# mcu-io.net
KiCad netlist of a schematic drawn in Altium Designer
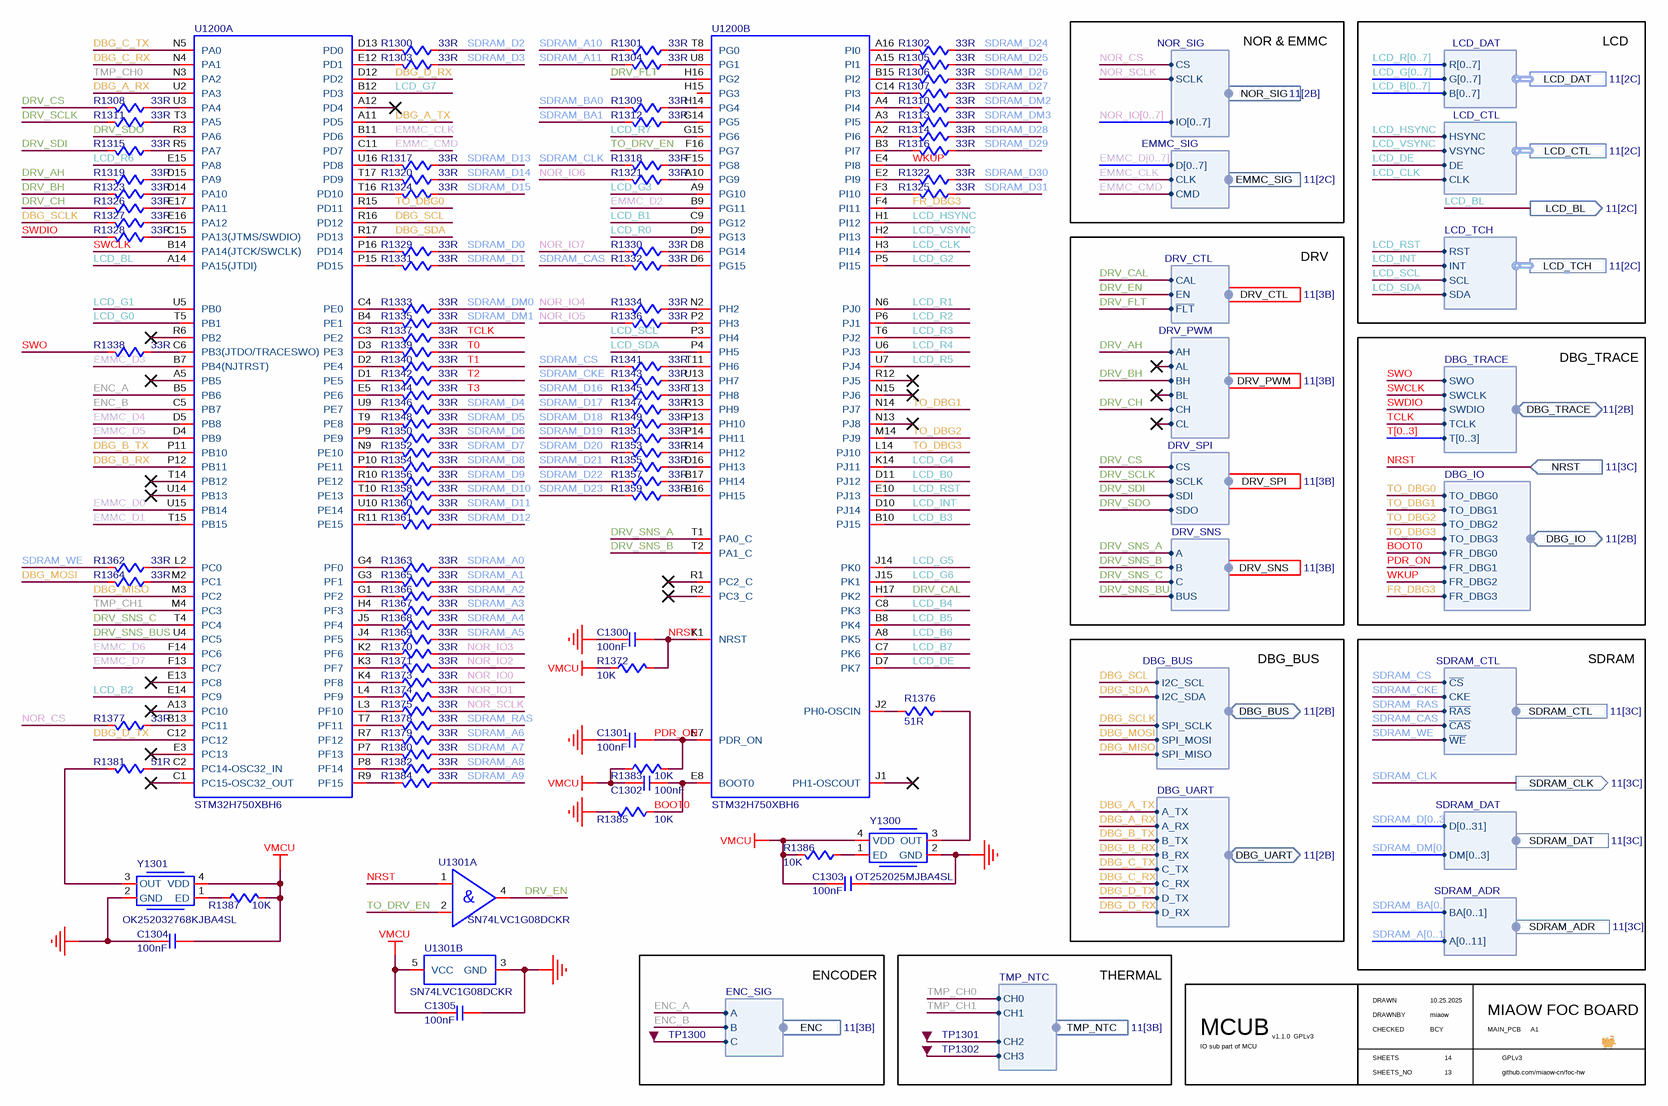
[diagram p0: mcu-io.schdoc]

(export (version "E")
  (design (tool "Eeschema 10.0.6"))
  (components
    (comp (ref "C1300")
      (value "100nF")
      (footprint "mw:C0402")
      (fields (field (name "VOLTAGE") "25V") (field (name "Comment") "C-NOMO"))
      (libsource (lib "mw") (part "C-NOMO"))
    )
    (comp (ref "C1301")
      (value "100nF")
      (footprint "mw:C0402")
      (fields (field (name "VOLTAGE") "25V") (field (name "Comment") "C-NOMO"))
      (libsource (lib "mw") (part "C-NOMO"))
    )
    (comp (ref "C1302")
      (value "100nF")
      (footprint "mw:C0402")
      (fields (field (name "VOLTAGE") "25V") (field (name "Comment") "C-NOMO"))
      (libsource (lib "mw") (part "C-NOMO"))
    )
    (comp (ref "C1303")
      (value "100nF")
      (footprint "mw:C0402")
      (fields (field (name "VOLTAGE") "25V") (field (name "Comment") "C-NOMO"))
      (libsource (lib "mw") (part "C-NOMO"))
    )
    (comp (ref "C1304")
      (value "100nF")
      (footprint "mw:C0402")
      (fields (field (name "VOLTAGE") "25V") (field (name "Comment") "C-NOMO"))
      (libsource (lib "mw") (part "C-NOMO"))
    )
    (comp (ref "C1305")
      (value "100nF")
      (footprint "mw:C0402")
      (fields (field (name "VOLTAGE") "25V") (field (name "Comment") "C-NOMO"))
      (libsource (lib "mw") (part "C-NOMO"))
    )
    (comp (ref "R1300")
      (value "33R")
      (footprint "mw:R0402")
      (fields (field (name "Comment") "R"))
      (libsource (lib "mw") (part "R"))
    )
    (comp (ref "R1301")
      (value "33R")
      (footprint "mw:R0402")
      (fields (field (name "Comment") "R"))
      (libsource (lib "mw") (part "R"))
    )
    (comp (ref "R1302")
      (value "33R")
      (footprint "mw:R0402")
      (fields (field (name "Comment") "R"))
      (libsource (lib "mw") (part "R"))
    )
    (comp (ref "R1303")
      (value "33R")
      (footprint "mw:R0402")
      (fields (field (name "Comment") "R"))
      (libsource (lib "mw") (part "R"))
    )
    (comp (ref "R1304")
      (value "33R")
      (footprint "mw:R0402")
      (fields (field (name "Comment") "R"))
      (libsource (lib "mw") (part "R"))
    )
    (comp (ref "R1305")
      (value "33R")
      (footprint "mw:R0402")
      (fields (field (name "Comment") "R"))
      (libsource (lib "mw") (part "R"))
    )
    (comp (ref "R1306")
      (value "33R")
      (footprint "mw:R0402")
      (fields (field (name "Comment") "R"))
      (libsource (lib "mw") (part "R"))
    )
    (comp (ref "R1307")
      (value "33R")
      (footprint "mw:R0402")
      (fields (field (name "Comment") "R"))
      (libsource (lib "mw") (part "R"))
    )
    (comp (ref "R1308")
      (value "33R")
      (footprint "mw:R0402")
      (fields (field (name "Comment") "R"))
      (libsource (lib "mw") (part "R"))
    )
    (comp (ref "R1309")
      (value "33R")
      (footprint "mw:R0402")
      (fields (field (name "Comment") "R"))
      (libsource (lib "mw") (part "R"))
    )
    (comp (ref "R1310")
      (value "33R")
      (footprint "mw:R0402")
      (fields (field (name "Comment") "R"))
      (libsource (lib "mw") (part "R"))
    )
    (comp (ref "R1311")
      (value "33R")
      (footprint "mw:R0402")
      (fields (field (name "Comment") "R"))
      (libsource (lib "mw") (part "R"))
    )
    (comp (ref "R1312")
      (value "33R")
      (footprint "mw:R0402")
      (fields (field (name "Comment") "R"))
      (libsource (lib "mw") (part "R"))
    )
    (comp (ref "R1313")
      (value "33R")
      (footprint "mw:R0402")
      (fields (field (name "Comment") "R"))
      (libsource (lib "mw") (part "R"))
    )
    (comp (ref "R1314")
      (value "33R")
      (footprint "mw:R0402")
      (fields (field (name "Comment") "R"))
      (libsource (lib "mw") (part "R"))
    )
    (comp (ref "R1315")
      (value "33R")
      (footprint "mw:R0402")
      (fields (field (name "Comment") "R"))
      (libsource (lib "mw") (part "R"))
    )
    (comp (ref "R1316")
      (value "33R")
      (footprint "mw:R0402")
      (fields (field (name "Comment") "R"))
      (libsource (lib "mw") (part "R"))
    )
    (comp (ref "R1317")
      (value "33R")
      (footprint "mw:R0402")
      (fields (field (name "Comment") "R"))
      (libsource (lib "mw") (part "R"))
    )
    (comp (ref "R1318")
      (value "33R")
      (footprint "mw:R0402")
      (fields (field (name "Comment") "R"))
      (libsource (lib "mw") (part "R"))
    )
    (comp (ref "R1319")
      (value "33R")
      (footprint "mw:R0402")
      (fields (field (name "Comment") "R"))
      (libsource (lib "mw") (part "R"))
    )
    (comp (ref "R1320")
      (value "33R")
      (footprint "mw:R0402")
      (fields (field (name "Comment") "R"))
      (libsource (lib "mw") (part "R"))
    )
    (comp (ref "R1321")
      (value "33R")
      (footprint "mw:R0402")
      (fields (field (name "Comment") "R"))
      (libsource (lib "mw") (part "R"))
    )
    (comp (ref "R1322")
      (value "33R")
      (footprint "mw:R0402")
      (fields (field (name "Comment") "R"))
      (libsource (lib "mw") (part "R"))
    )
    (comp (ref "R1323")
      (value "33R")
      (footprint "mw:R0402")
      (fields (field (name "Comment") "R"))
      (libsource (lib "mw") (part "R"))
    )
    (comp (ref "R1324")
      (value "33R")
      (footprint "mw:R0402")
      (fields (field (name "Comment") "R"))
      (libsource (lib "mw") (part "R"))
    )
    (comp (ref "R1325")
      (value "33R")
      (footprint "mw:R0402")
      (fields (field (name "Comment") "R"))
      (libsource (lib "mw") (part "R"))
    )
    (comp (ref "R1326")
      (value "33R")
      (footprint "mw:R0402")
      (fields (field (name "Comment") "R"))
      (libsource (lib "mw") (part "R"))
    )
    (comp (ref "R1327")
      (value "33R")
      (footprint "mw:R0402")
      (fields (field (name "Comment") "R"))
      (libsource (lib "mw") (part "R"))
    )
    (comp (ref "R1328")
      (value "33R")
      (footprint "mw:R0402")
      (fields (field (name "Comment") "R"))
      (libsource (lib "mw") (part "R"))
    )
    (comp (ref "R1329")
      (value "33R")
      (footprint "mw:R0402")
      (fields (field (name "Comment") "R"))
      (libsource (lib "mw") (part "R"))
    )
    (comp (ref "R1330")
      (value "33R")
      (footprint "mw:R0402")
      (fields (field (name "Comment") "R"))
      (libsource (lib "mw") (part "R"))
    )
    (comp (ref "R1331")
      (value "33R")
      (footprint "mw:R0402")
      (fields (field (name "Comment") "R"))
      (libsource (lib "mw") (part "R"))
    )
    (comp (ref "R1332")
      (value "33R")
      (footprint "mw:R0402")
      (fields (field (name "Comment") "R"))
      (libsource (lib "mw") (part "R"))
    )
    (comp (ref "R1333")
      (value "33R")
      (footprint "mw:R0402")
      (fields (field (name "Comment") "R"))
      (libsource (lib "mw") (part "R"))
    )
    (comp (ref "R1334")
      (value "33R")
      (footprint "mw:R0402")
      (fields (field (name "Comment") "R"))
      (libsource (lib "mw") (part "R"))
    )
    (comp (ref "R1335")
      (value "33R")
      (footprint "mw:R0402")
      (fields (field (name "Comment") "R"))
      (libsource (lib "mw") (part "R"))
    )
    (comp (ref "R1336")
      (value "33R")
      (footprint "mw:R0402")
      (fields (field (name "Comment") "R"))
      (libsource (lib "mw") (part "R"))
    )
    (comp (ref "R1337")
      (value "33R")
      (footprint "mw:R0402")
      (fields (field (name "Comment") "R"))
      (libsource (lib "mw") (part "R"))
    )
    (comp (ref "R1338")
      (value "33R")
      (footprint "mw:R0402")
      (fields (field (name "Comment") "R"))
      (libsource (lib "mw") (part "R"))
    )
    (comp (ref "R1339")
      (value "33R")
      (footprint "mw:R0402")
      (fields (field (name "Comment") "R"))
      (libsource (lib "mw") (part "R"))
    )
    (comp (ref "R1340")
      (value "33R")
      (footprint "mw:R0402")
      (fields (field (name "Comment") "R"))
      (libsource (lib "mw") (part "R"))
    )
    (comp (ref "R1341")
      (value "33R")
      (footprint "mw:R0402")
      (fields (field (name "Comment") "R"))
      (libsource (lib "mw") (part "R"))
    )
    (comp (ref "R1342")
      (value "33R")
      (footprint "mw:R0402")
      (fields (field (name "Comment") "R"))
      (libsource (lib "mw") (part "R"))
    )
    (comp (ref "R1343")
      (value "33R")
      (footprint "mw:R0402")
      (fields (field (name "Comment") "R"))
      (libsource (lib "mw") (part "R"))
    )
    (comp (ref "R1344")
      (value "33R")
      (footprint "mw:R0402")
      (fields (field (name "Comment") "R"))
      (libsource (lib "mw") (part "R"))
    )
    (comp (ref "R1345")
      (value "33R")
      (footprint "mw:R0402")
      (fields (field (name "Comment") "R"))
      (libsource (lib "mw") (part "R"))
    )
    (comp (ref "R1346")
      (value "33R")
      (footprint "mw:R0402")
      (fields (field (name "Comment") "R"))
      (libsource (lib "mw") (part "R"))
    )
    (comp (ref "R1347")
      (value "33R")
      (footprint "mw:R0402")
      (fields (field (name "Comment") "R"))
      (libsource (lib "mw") (part "R"))
    )
    (comp (ref "R1348")
      (value "33R")
      (footprint "mw:R0402")
      (fields (field (name "Comment") "R"))
      (libsource (lib "mw") (part "R"))
    )
    (comp (ref "R1349")
      (value "33R")
      (footprint "mw:R0402")
      (fields (field (name "Comment") "R"))
      (libsource (lib "mw") (part "R"))
    )
    (comp (ref "R1350")
      (value "33R")
      (footprint "mw:R0402")
      (fields (field (name "Comment") "R"))
      (libsource (lib "mw") (part "R"))
    )
    (comp (ref "R1351")
      (value "33R")
      (footprint "mw:R0402")
      (fields (field (name "Comment") "R"))
      (libsource (lib "mw") (part "R"))
    )
    (comp (ref "R1352")
      (value "33R")
      (footprint "mw:R0402")
      (fields (field (name "Comment") "R"))
      (libsource (lib "mw") (part "R"))
    )
    (comp (ref "R1353")
      (value "33R")
      (footprint "mw:R0402")
      (fields (field (name "Comment") "R"))
      (libsource (lib "mw") (part "R"))
    )
    (comp (ref "R1354")
      (value "33R")
      (footprint "mw:R0402")
      (fields (field (name "Comment") "R"))
      (libsource (lib "mw") (part "R"))
    )
    (comp (ref "R1355")
      (value "33R")
      (footprint "mw:R0402")
      (fields (field (name "Comment") "R"))
      (libsource (lib "mw") (part "R"))
    )
    (comp (ref "R1356")
      (value "33R")
      (footprint "mw:R0402")
      (fields (field (name "Comment") "R"))
      (libsource (lib "mw") (part "R"))
    )
    (comp (ref "R1357")
      (value "33R")
      (footprint "mw:R0402")
      (fields (field (name "Comment") "R"))
      (libsource (lib "mw") (part "R"))
    )
    (comp (ref "R1358")
      (value "33R")
      (footprint "mw:R0402")
      (fields (field (name "Comment") "R"))
      (libsource (lib "mw") (part "R"))
    )
    (comp (ref "R1359")
      (value "33R")
      (footprint "mw:R0402")
      (fields (field (name "Comment") "R"))
      (libsource (lib "mw") (part "R"))
    )
    (comp (ref "R1360")
      (value "33R")
      (footprint "mw:R0402")
      (fields (field (name "Comment") "R"))
      (libsource (lib "mw") (part "R"))
    )
    (comp (ref "R1361")
      (value "33R")
      (footprint "mw:R0402")
      (fields (field (name "Comment") "R"))
      (libsource (lib "mw") (part "R"))
    )
    (comp (ref "R1362")
      (value "33R")
      (footprint "mw:R0402")
      (fields (field (name "Comment") "R"))
      (libsource (lib "mw") (part "R"))
    )
    (comp (ref "R1363")
      (value "33R")
      (footprint "mw:R0402")
      (fields (field (name "Comment") "R"))
      (libsource (lib "mw") (part "R"))
    )
    (comp (ref "R1364")
      (value "33R")
      (footprint "mw:R0402")
      (fields (field (name "Comment") "R"))
      (libsource (lib "mw") (part "R"))
    )
    (comp (ref "R1365")
      (value "33R")
      (footprint "mw:R0402")
      (fields (field (name "Comment") "R"))
      (libsource (lib "mw") (part "R"))
    )
    (comp (ref "R1366")
      (value "33R")
      (footprint "mw:R0402")
      (fields (field (name "Comment") "R"))
      (libsource (lib "mw") (part "R"))
    )
    (comp (ref "R1367")
      (value "33R")
      (footprint "mw:R0402")
      (fields (field (name "Comment") "R"))
      (libsource (lib "mw") (part "R"))
    )
    (comp (ref "R1368")
      (value "33R")
      (footprint "mw:R0402")
      (fields (field (name "Comment") "R"))
      (libsource (lib "mw") (part "R"))
    )
    (comp (ref "R1369")
      (value "33R")
      (footprint "mw:R0402")
      (fields (field (name "Comment") "R"))
      (libsource (lib "mw") (part "R"))
    )
    (comp (ref "R1370")
      (value "33R")
      (footprint "mw:R0402")
      (fields (field (name "Comment") "R"))
      (libsource (lib "mw") (part "R"))
    )
    (comp (ref "R1371")
      (value "33R")
      (footprint "mw:R0402")
      (fields (field (name "Comment") "R"))
      (libsource (lib "mw") (part "R"))
    )
    (comp (ref "R1372")
      (value "10K")
      (footprint "mw:R0402")
      (fields (field (name "Comment") "R"))
      (libsource (lib "mw") (part "R"))
    )
    (comp (ref "R1373")
      (value "33R")
      (footprint "mw:R0402")
      (fields (field (name "Comment") "R"))
      (libsource (lib "mw") (part "R"))
    )
    (comp (ref "R1374")
      (value "33R")
      (footprint "mw:R0402")
      (fields (field (name "Comment") "R"))
      (libsource (lib "mw") (part "R"))
    )
    (comp (ref "R1375")
      (value "33R")
      (footprint "mw:R0402")
      (fields (field (name "Comment") "R"))
      (libsource (lib "mw") (part "R"))
    )
    (comp (ref "R1376")
      (value "51R")
      (footprint "mw:R0402")
      (fields (field (name "Comment") "R"))
      (libsource (lib "mw") (part "R"))
    )
    (comp (ref "R1377")
      (value "33R")
      (footprint "mw:R0402")
      (fields (field (name "Comment") "R"))
      (libsource (lib "mw") (part "R"))
    )
    (comp (ref "R1378")
      (value "33R")
      (footprint "mw:R0402")
      (fields (field (name "Comment") "R"))
      (libsource (lib "mw") (part "R"))
    )
    (comp (ref "R1379")
      (value "33R")
      (footprint "mw:R0402")
      (fields (field (name "Comment") "R"))
      (libsource (lib "mw") (part "R"))
    )
    (comp (ref "R1380")
      (value "33R")
      (footprint "mw:R0402")
      (fields (field (name "Comment") "R"))
      (libsource (lib "mw") (part "R"))
    )
    (comp (ref "R1381")
      (value "51R")
      (footprint "mw:R0402")
      (fields (field (name "Comment") "R"))
      (libsource (lib "mw") (part "R"))
    )
    (comp (ref "R1382")
      (value "33R")
      (footprint "mw:R0402")
      (fields (field (name "Comment") "R"))
      (libsource (lib "mw") (part "R"))
    )
    (comp (ref "R1383")
      (value "10K")
      (footprint "mw:R0402")
      (fields (field (name "Comment") "R"))
      (libsource (lib "mw") (part "R"))
    )
    (comp (ref "R1384")
      (value "33R")
      (footprint "mw:R0402")
      (fields (field (name "Comment") "R"))
      (libsource (lib "mw") (part "R"))
    )
    (comp (ref "R1385")
      (value "10K")
      (footprint "mw:R0402")
      (fields (field (name "Comment") "R"))
      (libsource (lib "mw") (part "R"))
    )
    (comp (ref "R1386")
      (value "10K")
      (footprint "mw:R0402")
      (fields (field (name "Comment") "R"))
      (libsource (lib "mw") (part "R"))
    )
    (comp (ref "R1387")
      (value "10K")
      (footprint "mw:R0402")
      (fields (field (name "Comment") "R"))
      (libsource (lib "mw") (part "R"))
    )
    (comp (ref "TP1300") (value "TP") (footprint "mw:TP") (libsource (lib "mw") (part "TP")))
    (comp (ref "TP1301") (value "TP") (footprint "mw:TP") (libsource (lib "mw") (part "TP")))
    (comp (ref "TP1302") (value "TP") (footprint "mw:TP") (libsource (lib "mw") (part "TP")))
    (comp (ref "U1200")
      (value "STM32H750XBH6")
      (footprint "mw:STM32H750XBH6")
      (description "MCU")
      (libsource (lib "mw") (part "STM32H750XBH6"))
    )
    (comp (ref "U1301")
      (value "SN74LVC1G08DCKR")
      (footprint "mw:SN74LVC1G08DCKR")
      (description "AND GATE  - 1bit")
      (libsource (lib "mw") (part "SN74LVC1G08DCKR"))
    )
    (comp (ref "Y1300")
      (value "OT252025MJBA4SL")
      (footprint "mw:OT252025MJBA4SL")
      (libsource (lib "mw") (part "OT252025MJBA4SL"))
    )
    (comp (ref "Y1301")
      (value "OK252032768KJBA4SL")
      (footprint "mw:OK252032768KJBA4SL")
      (libsource (lib "mw") (part "OK252032768KJBA4SL"))
    )
  )
  (nets
    (net (code "5") (name "/BOOT0") (class "Default")
      (node (ref "C1302") (pin "1") (pinfunction "1_1") (pintype "passive"))
      (node (ref "R1385") (pin "2") (pinfunction "2_2") (pintype "passive"))
      (node (ref "U1200") (pin "E8") (pinfunction "BOOT0_E8") (pintype "passive"))
    )
    (net (code "6") (name "/CH2") (class "Default") (node (ref "TP1301") (pin "0") (pintype "passive")))
    (net (code "7") (name "/CH3") (class "Default") (node (ref "TP1302") (pin "0") (pintype "passive")))
    (net (code "9") (name "/DBG_A_RX") (class "Default")
      (node (ref "U1200") (pin "U2") (pinfunction "PA3_U2") (pintype "passive"))
    )
    (net (code "10") (name "/DBG_A_TX") (class "Default")
      (node (ref "U1200") (pin "A11") (pinfunction "PD5_A11") (pintype "passive"))
    )
    (net (code "11") (name "/DBG_B_RX") (class "Default")
      (node (ref "U1200") (pin "P12") (pinfunction "PB11_P12") (pintype "passive"))
    )
    (net (code "12") (name "/DBG_B_TX") (class "Default")
      (node (ref "U1200") (pin "P11") (pinfunction "PB10_P11") (pintype "passive"))
    )
    (net (code "13") (name "/DBG_C_RX") (class "Default")
      (node (ref "U1200") (pin "N4") (pinfunction "PA1_N4") (pintype "passive"))
    )
    (net (code "14") (name "/DBG_C_TX") (class "Default")
      (node (ref "U1200") (pin "N5") (pinfunction "PA0_N5") (pintype "passive"))
    )
    (net (code "15") (name "/DBG_D_RX") (class "Default")
      (node (ref "U1200") (pin "D12") (pinfunction "PD2_D12") (pintype "passive"))
    )
    (net (code "16") (name "/DBG_D_TX") (class "Default")
      (node (ref "U1200") (pin "C12") (pinfunction "PC12_C12") (pintype "passive"))
    )
    (net (code "17") (name "/DBG_MISO") (class "Default")
      (node (ref "U1200") (pin "M3") (pinfunction "PC2_M3") (pintype "passive"))
    )
    (net (code "18") (name "/DBG_MOSI") (class "Default")
      (node (ref "R1364") (pin "2") (pinfunction "2_2") (pintype "passive"))
    )
    (net (code "19") (name "/DBG_SCL") (class "Default")
      (node (ref "U1200") (pin "R16") (pinfunction "PD12_R16") (pintype "passive"))
    )
    (net (code "20") (name "/DBG_SCLK") (class "Default")
      (node (ref "R1327") (pin "2") (pinfunction "2_2") (pintype "passive"))
    )
    (net (code "21") (name "/DBG_SDA") (class "Default")
      (node (ref "U1200") (pin "R17") (pinfunction "PD13_R17") (pintype "passive"))
    )
    (net (code "22") (name "/DRV_AH") (class "Default")
      (node (ref "R1319") (pin "2") (pinfunction "2_2") (pintype "passive"))
    )
    (net (code "23") (name "/DRV_BH") (class "Default")
      (node (ref "R1323") (pin "2") (pinfunction "2_2") (pintype "passive"))
    )
    (net (code "24") (name "/DRV_CAL") (class "Default")
      (node (ref "U1200") (pin "H17") (pinfunction "PK2_H17") (pintype "passive"))
    )
    (net (code "25") (name "/DRV_CH") (class "Default")
      (node (ref "R1326") (pin "2") (pinfunction "2_2") (pintype "passive"))
    )
    (net (code "26") (name "/DRV_CS") (class "Default")
      (node (ref "R1308") (pin "2") (pinfunction "2_2") (pintype "passive"))
    )
    (net (code "27") (name "/DRV_EN") (class "Default")
      (node (ref "U1301") (pin "4") (pinfunction "Y_4") (pintype "passive"))
    )
    (net (code "28") (name "/DRV_FLT") (class "Default")
      (node (ref "U1200") (pin "H16") (pinfunction "PG2_H16") (pintype "passive"))
    )
    (net (code "29") (name "/DRV_SCLK") (class "Default")
      (node (ref "R1311") (pin "2") (pinfunction "2_2") (pintype "passive"))
    )
    (net (code "30") (name "/DRV_SDI") (class "Default")
      (node (ref "R1315") (pin "2") (pinfunction "2_2") (pintype "passive"))
    )
    (net (code "31") (name "/DRV_SDO") (class "Default")
      (node (ref "U1200") (pin "R3") (pinfunction "PA6_R3") (pintype "passive"))
    )
    (net (code "32") (name "/DRV_SNS_A") (class "Default")
      (node (ref "U1200") (pin "T1") (pinfunction "PA0_C_T1") (pintype "passive"))
    )
    (net (code "33") (name "/DRV_SNS_B") (class "Default")
      (node (ref "U1200") (pin "T2") (pinfunction "PA1_C_T2") (pintype "passive"))
    )
    (net (code "34") (name "/DRV_SNS_BUS") (class "Default")
      (node (ref "U1200") (pin "U4") (pinfunction "PC5_U4") (pintype "passive"))
    )
    (net (code "35") (name "/DRV_SNS_C") (class "Default")
      (node (ref "U1200") (pin "T4") (pinfunction "PC4_T4") (pintype "passive"))
    )
    (net (code "36") (name "/EMMC_CLK") (class "Default")
      (node (ref "U1200") (pin "B11") (pinfunction "PD6_B11") (pintype "passive"))
    )
    (net (code "37") (name "/EMMC_CMD") (class "Default")
      (node (ref "U1200") (pin "C11") (pinfunction "PD7_C11") (pintype "passive"))
    )
    (net (code "38") (name "/EMMC_D0") (class "Default")
      (node (ref "U1200") (pin "U15") (pinfunction "PB14_U15") (pintype "passive"))
    )
    (net (code "39") (name "/EMMC_D1") (class "Default")
      (node (ref "U1200") (pin "T15") (pinfunction "PB15_T15") (pintype "passive"))
    )
    (net (code "40") (name "/EMMC_D2") (class "Default")
      (node (ref "U1200") (pin "B9") (pinfunction "PG11_B9") (pintype "passive"))
    )
    (net (code "41") (name "/EMMC_D3") (class "Default")
      (node (ref "U1200") (pin "B7") (pinfunction "PB4(NJTRST)_B7") (pintype "passive"))
    )
    (net (code "42") (name "/EMMC_D4") (class "Default")
      (node (ref "U1200") (pin "D5") (pinfunction "PB8_D5") (pintype "passive"))
    )
    (net (code "43") (name "/EMMC_D5") (class "Default")
      (node (ref "U1200") (pin "D4") (pinfunction "PB9_D4") (pintype "passive"))
    )
    (net (code "44") (name "/EMMC_D6") (class "Default")
      (node (ref "U1200") (pin "F14") (pinfunction "PC6_F14") (pintype "passive"))
    )
    (net (code "45") (name "/EMMC_D7") (class "Default")
      (node (ref "U1200") (pin "F13") (pinfunction "PC7_F13") (pintype "passive"))
    )
    (net (code "46") (name "/ENC_A") (class "Default")
      (node (ref "U1200") (pin "B5") (pinfunction "PB6_B5") (pintype "passive"))
    )
    (net (code "47") (name "/ENC_B") (class "Default")
      (node (ref "U1200") (pin "C5") (pinfunction "PB7_C5") (pintype "passive"))
    )
    (net (code "48") (name "/FR_DBG3") (class "Default")
      (node (ref "U1200") (pin "F4") (pinfunction "PI11_F4") (pintype "passive"))
    )
    (net (code "49") (name "/LCD_B0") (class "Default")
      (node (ref "U1200") (pin "D11") (pinfunction "PJ12_D11") (pintype "passive"))
    )
    (net (code "50") (name "/LCD_B1") (class "Default")
      (node (ref "U1200") (pin "C9") (pinfunction "PG12_C9") (pintype "passive"))
    )
    (net (code "51") (name "/LCD_B2") (class "Default")
      (node (ref "U1200") (pin "E14") (pinfunction "PC9_E14") (pintype "passive"))
    )
    (net (code "52") (name "/LCD_B3") (class "Default")
      (node (ref "U1200") (pin "B10") (pinfunction "PJ15_B10") (pintype "passive"))
    )
    (net (code "53") (name "/LCD_B4") (class "Default")
      (node (ref "U1200") (pin "C8") (pinfunction "PK3_C8") (pintype "passive"))
    )
    (net (code "54") (name "/LCD_B5") (class "Default")
      (node (ref "U1200") (pin "B8") (pinfunction "PK4_B8") (pintype "passive"))
    )
    (net (code "55") (name "/LCD_B6") (class "Default")
      (node (ref "U1200") (pin "A8") (pinfunction "PK5_A8") (pintype "passive"))
    )
    (net (code "56") (name "/LCD_B7") (class "Default")
      (node (ref "U1200") (pin "C7") (pinfunction "PK6_C7") (pintype "passive"))
    )
    (net (code "57") (name "/LCD_BL") (class "Default")
      (node (ref "U1200") (pin "A14") (pinfunction "PA15(JTDI)_A14") (pintype "passive"))
    )
    (net (code "58") (name "/LCD_CLK") (class "Default")
      (node (ref "U1200") (pin "H3") (pinfunction "PI14_H3") (pintype "passive"))
    )
    (net (code "59") (name "/LCD_DE") (class "Default")
      (node (ref "U1200") (pin "D7") (pinfunction "PK7_D7") (pintype "passive"))
    )
    (net (code "60") (name "/LCD_G0") (class "Default")
      (node (ref "U1200") (pin "T5") (pinfunction "PB1_T5") (pintype "passive"))
    )
    (net (code "61") (name "/LCD_G1") (class "Default")
      (node (ref "U1200") (pin "U5") (pinfunction "PB0_U5") (pintype "passive"))
    )
    (net (code "62") (name "/LCD_G2") (class "Default")
      (node (ref "U1200") (pin "P5") (pinfunction "PI15_P5") (pintype "passive"))
    )
    (net (code "63") (name "/LCD_G3") (class "Default")
      (node (ref "U1200") (pin "A9") (pinfunction "PG10_A9") (pintype "passive"))
    )
    (net (code "64") (name "/LCD_G4") (class "Default")
      (node (ref "U1200") (pin "K14") (pinfunction "PJ11_K14") (pintype "passive"))
    )
    (net (code "65") (name "/LCD_G5") (class "Default")
      (node (ref "U1200") (pin "J14") (pinfunction "PK0_J14") (pintype "passive"))
    )
    (net (code "66") (name "/LCD_G6") (class "Default")
      (node (ref "U1200") (pin "J15") (pinfunction "PK1_J15") (pintype "passive"))
    )
    (net (code "67") (name "/LCD_G7") (class "Default")
      (node (ref "U1200") (pin "B12") (pinfunction "PD3_B12") (pintype "passive"))
    )
    (net (code "69") (name "/LCD_HSYNC") (class "Default")
      (node (ref "U1200") (pin "H1") (pinfunction "PI12_H1") (pintype "passive"))
    )
    (net (code "70") (name "/LCD_INT") (class "Default")
      (node (ref "U1200") (pin "D10") (pinfunction "PJ14_D10") (pintype "passive"))
    )
    (net (code "71") (name "/LCD_R0") (class "Default")
      (node (ref "U1200") (pin "D9") (pinfunction "PG13_D9") (pintype "passive"))
    )
    (net (code "72") (name "/LCD_R1") (class "Default")
      (node (ref "U1200") (pin "N6") (pinfunction "PJ0_N6") (pintype "passive"))
    )
    (net (code "73") (name "/LCD_R2") (class "Default")
      (node (ref "U1200") (pin "P6") (pinfunction "PJ1_P6") (pintype "passive"))
    )
    (net (code "74") (name "/LCD_R3") (class "Default")
      (node (ref "U1200") (pin "T6") (pinfunction "PJ2_T6") (pintype "passive"))
    )
    (net (code "75") (name "/LCD_R4") (class "Default")
      (node (ref "U1200") (pin "U6") (pinfunction "PJ3_U6") (pintype "passive"))
    )
    (net (code "76") (name "/LCD_R5") (class "Default")
      (node (ref "U1200") (pin "U7") (pinfunction "PJ4_U7") (pintype "passive"))
    )
    (net (code "77") (name "/LCD_R6") (class "Default")
      (node (ref "U1200") (pin "E15") (pinfunction "PA8_E15") (pintype "passive"))
    )
    (net (code "78") (name "/LCD_R7") (class "Default")
      (node (ref "U1200") (pin "G15") (pinfunction "PG6_G15") (pintype "passive"))
    )
    (net (code "79") (name "/LCD_RST") (class "Default")
      (node (ref "U1200") (pin "E10") (pinfunction "PJ13_E10") (pintype "passive"))
    )
    (net (code "81") (name "/LCD_SCL") (class "Default")
      (node (ref "U1200") (pin "P3") (pinfunction "PH4_P3") (pintype "passive"))
    )
    (net (code "82") (name "/LCD_SDA") (class "Default")
      (node (ref "U1200") (pin "P4") (pinfunction "PH5_P4") (pintype "passive"))
    )
    (net (code "83") (name "/LCD_VSYNC") (class "Default")
      (node (ref "U1200") (pin "H2") (pinfunction "PI13_H2") (pintype "passive"))
    )
    (net (code "84") (name "/NOR_CS") (class "Default")
      (node (ref "R1377") (pin "2") (pinfunction "2_2") (pintype "passive"))
    )
    (net (code "85") (name "/NOR_IO0") (class "Default")
      (node (ref "R1373") (pin "2") (pinfunction "2_2") (pintype "passive"))
    )
    (net (code "86") (name "/NOR_IO1") (class "Default")
      (node (ref "R1374") (pin "2") (pinfunction "2_2") (pintype "passive"))
    )
    (net (code "87") (name "/NOR_IO2") (class "Default")
      (node (ref "R1371") (pin "2") (pinfunction "2_2") (pintype "passive"))
    )
    (net (code "88") (name "/NOR_IO3") (class "Default")
      (node (ref "R1370") (pin "2") (pinfunction "2_2") (pintype "passive"))
    )
    (net (code "89") (name "/NOR_IO4") (class "Default")
      (node (ref "R1334") (pin "2") (pinfunction "2_2") (pintype "passive"))
    )
    (net (code "90") (name "/NOR_IO5") (class "Default")
      (node (ref "R1336") (pin "2") (pinfunction "2_2") (pintype "passive"))
    )
    (net (code "91") (name "/NOR_IO6") (class "Default")
      (node (ref "R1321") (pin "2") (pinfunction "2_2") (pintype "passive"))
    )
    (net (code "92") (name "/NOR_IO7") (class "Default")
      (node (ref "R1330") (pin "2") (pinfunction "2_2") (pintype "passive"))
    )
    (net (code "93") (name "/NOR_SCLK") (class "Default")
      (node (ref "R1375") (pin "2") (pinfunction "2_2") (pintype "passive"))
    )
    (net (code "94") (name "/NRST") (class "Default")
      (node (ref "C1300") (pin "1") (pinfunction "1_1") (pintype "passive"))
      (node (ref "R1372") (pin "2") (pinfunction "2_2") (pintype "passive"))
      (node (ref "U1200") (pin "K1") (pinfunction "NRST_K1") (pintype "passive"))
      (node (ref "U1301") (pin "1") (pinfunction "A_1") (pintype "passive"))
    )
    (net (code "95") (name "/PDR_ON") (class "Default")
      (node (ref "C1301") (pin "1") (pinfunction "1_1") (pintype "passive"))
      (node (ref "R1383") (pin "1") (pinfunction "1_1") (pintype "passive"))
      (node (ref "U1200") (pin "E7") (pinfunction "PDR_ON_E7") (pintype "passive"))
    )
    (net (code "96") (name "/SDRAM_A0") (class "Default")
      (node (ref "R1363") (pin "2") (pinfunction "2_2") (pintype "passive"))
    )
    (net (code "97") (name "/SDRAM_A1") (class "Default")
      (node (ref "R1365") (pin "2") (pinfunction "2_2") (pintype "passive"))
    )
    (net (code "98") (name "/SDRAM_A2") (class "Default")
      (node (ref "R1366") (pin "2") (pinfunction "2_2") (pintype "passive"))
    )
    (net (code "99") (name "/SDRAM_A3") (class "Default")
      (node (ref "R1367") (pin "2") (pinfunction "2_2") (pintype "passive"))
    )
    (net (code "100") (name "/SDRAM_A4") (class "Default")
      (node (ref "R1368") (pin "2") (pinfunction "2_2") (pintype "passive"))
    )
    (net (code "101") (name "/SDRAM_A5") (class "Default")
      (node (ref "R1369") (pin "2") (pinfunction "2_2") (pintype "passive"))
    )
    (net (code "102") (name "/SDRAM_A6") (class "Default")
      (node (ref "R1379") (pin "2") (pinfunction "2_2") (pintype "passive"))
    )
    (net (code "103") (name "/SDRAM_A7") (class "Default")
      (node (ref "R1380") (pin "2") (pinfunction "2_2") (pintype "passive"))
    )
    (net (code "104") (name "/SDRAM_A8") (class "Default")
      (node (ref "R1382") (pin "2") (pinfunction "2_2") (pintype "passive"))
    )
    (net (code "105") (name "/SDRAM_A9") (class "Default")
      (node (ref "R1384") (pin "2") (pinfunction "2_2") (pintype "passive"))
    )
    (net (code "106") (name "/SDRAM_A10") (class "Default")
      (node (ref "R1301") (pin "2") (pinfunction "2_2") (pintype "passive"))
    )
    (net (code "107") (name "/SDRAM_A11") (class "Default")
      (node (ref "R1304") (pin "2") (pinfunction "2_2") (pintype "passive"))
    )
    (net (code "108") (name "/SDRAM_BA0") (class "Default")
      (node (ref "R1309") (pin "2") (pinfunction "2_2") (pintype "passive"))
    )
    (net (code "109") (name "/SDRAM_BA1") (class "Default")
      (node (ref "R1312") (pin "2") (pinfunction "2_2") (pintype "passive"))
    )
    (net (code "111") (name "/SDRAM_CAS") (class "Default")
      (node (ref "R1332") (pin "2") (pinfunction "2_2") (pintype "passive"))
    )
    (net (code "112") (name "/SDRAM_CKE") (class "Default")
      (node (ref "R1343") (pin "2") (pinfunction "2_2") (pintype "passive"))
    )
    (net (code "113") (name "/SDRAM_CLK") (class "Default")
      (node (ref "R1318") (pin "2") (pinfunction "2_2") (pintype "passive"))
    )
    (net (code "114") (name "/SDRAM_CS") (class "Default")
      (node (ref "R1341") (pin "2") (pinfunction "2_2") (pintype "passive"))
    )
    (net (code "115") (name "/SDRAM_D0") (class "Default")
      (node (ref "R1329") (pin "2") (pinfunction "2_2") (pintype "passive"))
    )
    (net (code "116") (name "/SDRAM_D1") (class "Default")
      (node (ref "R1331") (pin "2") (pinfunction "2_2") (pintype "passive"))
    )
    (net (code "117") (name "/SDRAM_D2") (class "Default")
      (node (ref "R1300") (pin "2") (pinfunction "2_2") (pintype "passive"))
    )
    (net (code "118") (name "/SDRAM_D3") (class "Default")
      (node (ref "R1303") (pin "2") (pinfunction "2_2") (pintype "passive"))
    )
    (net (code "119") (name "/SDRAM_D4") (class "Default")
      (node (ref "R1346") (pin "2") (pinfunction "2_2") (pintype "passive"))
    )
    (net (code "120") (name "/SDRAM_D5") (class "Default")
      (node (ref "R1348") (pin "2") (pinfunction "2_2") (pintype "passive"))
    )
    (net (code "121") (name "/SDRAM_D6") (class "Default")
      (node (ref "R1350") (pin "2") (pinfunction "2_2") (pintype "passive"))
    )
    (net (code "122") (name "/SDRAM_D7") (class "Default")
      (node (ref "R1352") (pin "2") (pinfunction "2_2") (pintype "passive"))
    )
    (net (code "123") (name "/SDRAM_D8") (class "Default")
      (node (ref "R1354") (pin "2") (pinfunction "2_2") (pintype "passive"))
    )
    (net (code "124") (name "/SDRAM_D9") (class "Default")
      (node (ref "R1356") (pin "2") (pinfunction "2_2") (pintype "passive"))
    )
    (net (code "125") (name "/SDRAM_D10") (class "Default")
      (node (ref "R1358") (pin "2") (pinfunction "2_2") (pintype "passive"))
    )
    (net (code "126") (name "/SDRAM_D11") (class "Default")
      (node (ref "R1360") (pin "2") (pinfunction "2_2") (pintype "passive"))
    )
    (net (code "127") (name "/SDRAM_D12") (class "Default")
      (node (ref "R1361") (pin "2") (pinfunction "2_2") (pintype "passive"))
    )
    (net (code "128") (name "/SDRAM_D13") (class "Default")
      (node (ref "R1317") (pin "2") (pinfunction "2_2") (pintype "passive"))
    )
    (net (code "129") (name "/SDRAM_D14") (class "Default")
      (node (ref "R1320") (pin "2") (pinfunction "2_2") (pintype "passive"))
    )
    (net (code "130") (name "/SDRAM_D15") (class "Default")
      (node (ref "R1324") (pin "2") (pinfunction "2_2") (pintype "passive"))
    )
    (net (code "131") (name "/SDRAM_D16") (class "Default")
      (node (ref "R1345") (pin "2") (pinfunction "2_2") (pintype "passive"))
    )
    (net (code "132") (name "/SDRAM_D17") (class "Default")
      (node (ref "R1347") (pin "2") (pinfunction "2_2") (pintype "passive"))
    )
    (net (code "133") (name "/SDRAM_D18") (class "Default")
      (node (ref "R1349") (pin "2") (pinfunction "2_2") (pintype "passive"))
    )
    (net (code "134") (name "/SDRAM_D19") (class "Default")
      (node (ref "R1351") (pin "2") (pinfunction "2_2") (pintype "passive"))
    )
    (net (code "135") (name "/SDRAM_D20") (class "Default")
      (node (ref "R1353") (pin "2") (pinfunction "2_2") (pintype "passive"))
    )
    (net (code "136") (name "/SDRAM_D21") (class "Default")
      (node (ref "R1355") (pin "2") (pinfunction "2_2") (pintype "passive"))
    )
    (net (code "137") (name "/SDRAM_D22") (class "Default")
      (node (ref "R1357") (pin "2") (pinfunction "2_2") (pintype "passive"))
    )
    (net (code "138") (name "/SDRAM_D23") (class "Default")
      (node (ref "R1359") (pin "2") (pinfunction "2_2") (pintype "passive"))
    )
    (net (code "139") (name "/SDRAM_D24") (class "Default")
      (node (ref "R1302") (pin "2") (pinfunction "2_2") (pintype "passive"))
    )
    (net (code "140") (name "/SDRAM_D25") (class "Default")
      (node (ref "R1305") (pin "2") (pinfunction "2_2") (pintype "passive"))
    )
    (net (code "141") (name "/SDRAM_D26") (class "Default")
      (node (ref "R1306") (pin "2") (pinfunction "2_2") (pintype "passive"))
    )
    (net (code "142") (name "/SDRAM_D27") (class "Default")
      (node (ref "R1307") (pin "2") (pinfunction "2_2") (pintype "passive"))
    )
    (net (code "143") (name "/SDRAM_D28") (class "Default")
      (node (ref "R1314") (pin "2") (pinfunction "2_2") (pintype "passive"))
    )
    (net (code "144") (name "/SDRAM_D29") (class "Default")
      (node (ref "R1316") (pin "2") (pinfunction "2_2") (pintype "passive"))
    )
    (net (code "145") (name "/SDRAM_D30") (class "Default")
      (node (ref "R1322") (pin "2") (pinfunction "2_2") (pintype "passive"))
    )
    (net (code "146") (name "/SDRAM_D31") (class "Default")
      (node (ref "R1325") (pin "2") (pinfunction "2_2") (pintype "passive"))
    )
    (net (code "147") (name "/SDRAM_DM0") (class "Default")
      (node (ref "R1333") (pin "2") (pinfunction "2_2") (pintype "passive"))
    )
    (net (code "148") (name "/SDRAM_DM1") (class "Default")
      (node (ref "R1335") (pin "2") (pinfunction "2_2") (pintype "passive"))
    )
    (net (code "149") (name "/SDRAM_DM2") (class "Default")
      (node (ref "R1310") (pin "2") (pinfunction "2_2") (pintype "passive"))
    )
    (net (code "150") (name "/SDRAM_DM3") (class "Default")
      (node (ref "R1313") (pin "2") (pinfunction "2_2") (pintype "passive"))
    )
    (net (code "152") (name "/SDRAM_RAS") (class "Default")
      (node (ref "R1378") (pin "2") (pinfunction "2_2") (pintype "passive"))
    )
    (net (code "153") (name "/SDRAM_WE") (class "Default")
      (node (ref "R1362") (pin "2") (pinfunction "2_2") (pintype "passive"))
    )
    (net (code "154") (name "/SWCLK") (class "Default")
      (node (ref "U1200") (pin "B14") (pinfunction "PA14(JTCK/SWCLK)_B14") (pintype "passive"))
    )
    (net (code "155") (name "/SWDIO") (class "Default")
      (node (ref "R1328") (pin "2") (pinfunction "2_2") (pintype "passive"))
    )
    (net (code "156") (name "/SWO") (class "Default")
      (node (ref "R1338") (pin "2") (pinfunction "2_2") (pintype "passive"))
    )
    (net (code "157") (name "/T0") (class "Default")
      (node (ref "R1339") (pin "2") (pinfunction "2_2") (pintype "passive"))
    )
    (net (code "158") (name "/T1") (class "Default")
      (node (ref "R1340") (pin "2") (pinfunction "2_2") (pintype "passive"))
    )
    (net (code "159") (name "/T2") (class "Default")
      (node (ref "R1342") (pin "2") (pinfunction "2_2") (pintype "passive"))
    )
    (net (code "160") (name "/T3") (class "Default")
      (node (ref "R1344") (pin "2") (pinfunction "2_2") (pintype "passive"))
    )
    (net (code "161") (name "/TCLK") (class "Default")
      (node (ref "R1337") (pin "2") (pinfunction "2_2") (pintype "passive"))
    )
    (net (code "162") (name "/TMP_CH0") (class "Default")
      (node (ref "U1200") (pin "N3") (pinfunction "PA2_N3") (pintype "passive"))
    )
    (net (code "163") (name "/TMP_CH1") (class "Default")
      (node (ref "U1200") (pin "M4") (pinfunction "PC3_M4") (pintype "passive"))
    )
    (net (code "164") (name "/TO_DBG0") (class "Default")
      (node (ref "U1200") (pin "R15") (pinfunction "PD11_R15") (pintype "passive"))
    )
    (net (code "165") (name "/TO_DBG1") (class "Default")
      (node (ref "U1200") (pin "N14") (pinfunction "PJ7_N14") (pintype "passive"))
    )
    (net (code "166") (name "/TO_DBG2") (class "Default")
      (node (ref "U1200") (pin "M14") (pinfunction "PJ9_M14") (pintype "passive"))
    )
    (net (code "167") (name "/TO_DBG3") (class "Default")
      (node (ref "U1200") (pin "L14") (pinfunction "PJ10_L14") (pintype "passive"))
    )
    (net (code "168") (name "/TO_DRV_EN") (class "Default")
      (node (ref "U1200") (pin "F16") (pinfunction "PG7_F16") (pintype "passive"))
      (node (ref "U1301") (pin "2") (pinfunction "B_2") (pintype "passive"))
    )
    (net (code "169") (name "/WKUP") (class "Default")
      (node (ref "U1200") (pin "E4") (pinfunction "PI8_E4") (pintype "passive"))
    )
    (net (code "177") (name "GND") (class "Default")
      (node (ref "C1300") (pin "2") (pinfunction "2_2") (pintype "passive"))
      (node (ref "C1301") (pin "2") (pinfunction "2_2") (pintype "passive"))
      (node (ref "C1303") (pin "2") (pinfunction "2_2") (pintype "passive"))
      (node (ref "C1304") (pin "2") (pinfunction "2_2") (pintype "passive"))
      (node (ref "C1305") (pin "2") (pinfunction "2_2") (pintype "passive"))
      (node (ref "R1385") (pin "1") (pinfunction "1_1") (pintype "passive"))
      (node (ref "U1301") (pin "3") (pinfunction "GND_3") (pintype "passive"))
      (node (ref "Y1300") (pin "2") (pinfunction "GND_2") (pintype "passive"))
      (node (ref "Y1301") (pin "2") (pinfunction "GND_2") (pintype "passive"))
    )
    (net (code "178") (name "Net-(U1200A-PA4)") (class "Default")
      (node (ref "R1308") (pin "1") (pinfunction "1_1") (pintype "passive"))
      (node (ref "U1200") (pin "U3") (pinfunction "PA4_U3") (pintype "passive"))
    )
    (net (code "179") (name "Net-(U1200A-PA5)") (class "Default")
      (node (ref "R1311") (pin "1") (pinfunction "1_1") (pintype "passive"))
      (node (ref "U1200") (pin "T3") (pinfunction "PA5_T3") (pintype "passive"))
    )
    (net (code "180") (name "Net-(U1200A-PA7)") (class "Default")
      (node (ref "R1315") (pin "1") (pinfunction "1_1") (pintype "passive"))
      (node (ref "U1200") (pin "R5") (pinfunction "PA7_R5") (pintype "passive"))
    )
    (net (code "181") (name "Net-(U1200A-PA9)") (class "Default")
      (node (ref "R1319") (pin "1") (pinfunction "1_1") (pintype "passive"))
      (node (ref "U1200") (pin "D15") (pinfunction "PA9_D15") (pintype "passive"))
    )
    (net (code "182") (name "Net-(U1200A-PA10)") (class "Default")
      (node (ref "R1323") (pin "1") (pinfunction "1_1") (pintype "passive"))
      (node (ref "U1200") (pin "D14") (pinfunction "PA10_D14") (pintype "passive"))
    )
    (net (code "183") (name "Net-(U1200A-PA11)") (class "Default")
      (node (ref "R1326") (pin "1") (pinfunction "1_1") (pintype "passive"))
      (node (ref "U1200") (pin "E17") (pinfunction "PA11_E17") (pintype "passive"))
    )
    (net (code "184") (name "Net-(U1200A-PA12)") (class "Default")
      (node (ref "R1327") (pin "1") (pinfunction "1_1") (pintype "passive"))
      (node (ref "U1200") (pin "E16") (pinfunction "PA12_E16") (pintype "passive"))
    )
    (net (code "185") (name "Net-(U1200A-PA13(JTMS{slash}SWDIO))") (class "Default")
      (node (ref "R1328") (pin "1") (pinfunction "1_1") (pintype "passive"))
      (node (ref "U1200") (pin "C15") (pinfunction "PA13(JTMS/SWDIO)_C15") (pintype "passive"))
    )
    (net (code "186") (name "Net-(U1200A-PB3(JTDO{slash}TRACESWO))") (class "Default")
      (node (ref "R1338") (pin "1") (pinfunction "1_1") (pintype "passive"))
      (node (ref "U1200") (pin "C6") (pinfunction "PB3(JTDO/TRACESWO)_C6") (pintype "passive"))
    )
    (net (code "187") (name "Net-(U1200A-PC0)") (class "Default")
      (node (ref "R1362") (pin "1") (pinfunction "1_1") (pintype "passive"))
      (node (ref "U1200") (pin "L2") (pinfunction "PC0_L2") (pintype "passive"))
    )
    (net (code "188") (name "Net-(U1200A-PC1)") (class "Default")
      (node (ref "R1364") (pin "1") (pinfunction "1_1") (pintype "passive"))
      (node (ref "U1200") (pin "M2") (pinfunction "PC1_M2") (pintype "passive"))
    )
    (net (code "189") (name "Net-(U1200A-PC11)") (class "Default")
      (node (ref "R1377") (pin "1") (pinfunction "1_1") (pintype "passive"))
      (node (ref "U1200") (pin "B13") (pinfunction "PC11_B13") (pintype "passive"))
    )
    (net (code "190") (name "Net-(U1200A-PC14-OSC32_IN)") (class "Default")
      (node (ref "R1381") (pin "2") (pinfunction "2_2") (pintype "passive"))
      (node (ref "U1200") (pin "C2") (pinfunction "PC14-OSC32_IN_C2") (pintype "passive"))
    )
    (net (code "191") (name "Net-(U1200A-PD0)") (class "Default")
      (node (ref "R1300") (pin "1") (pinfunction "1_1") (pintype "passive"))
      (node (ref "U1200") (pin "D13") (pinfunction "PD0_D13") (pintype "passive"))
    )
    (net (code "192") (name "Net-(U1200A-PD1)") (class "Default")
      (node (ref "R1303") (pin "1") (pinfunction "1_1") (pintype "passive"))
      (node (ref "U1200") (pin "E12") (pinfunction "PD1_E12") (pintype "passive"))
    )
    (net (code "193") (name "Net-(U1200A-PD8)") (class "Default")
      (node (ref "R1317") (pin "1") (pinfunction "1_1") (pintype "passive"))
      (node (ref "U1200") (pin "U16") (pinfunction "PD8_U16") (pintype "passive"))
    )
    (net (code "194") (name "Net-(U1200A-PD9)") (class "Default")
      (node (ref "R1320") (pin "1") (pinfunction "1_1") (pintype "passive"))
      (node (ref "U1200") (pin "T17") (pinfunction "PD9_T17") (pintype "passive"))
    )
    (net (code "195") (name "Net-(U1200A-PD10)") (class "Default")
      (node (ref "R1324") (pin "1") (pinfunction "1_1") (pintype "passive"))
      (node (ref "U1200") (pin "T16") (pinfunction "PD10_T16") (pintype "passive"))
    )
    (net (code "196") (name "Net-(U1200A-PD14)") (class "Default")
      (node (ref "R1329") (pin "1") (pinfunction "1_1") (pintype "passive"))
      (node (ref "U1200") (pin "P16") (pinfunction "PD14_P16") (pintype "passive"))
    )
    (net (code "197") (name "Net-(U1200A-PD15)") (class "Default")
      (node (ref "R1331") (pin "1") (pinfunction "1_1") (pintype "passive"))
      (node (ref "U1200") (pin "P15") (pinfunction "PD15_P15") (pintype "passive"))
    )
    (net (code "198") (name "Net-(U1200A-PE0)") (class "Default")
      (node (ref "R1333") (pin "1") (pinfunction "1_1") (pintype "passive"))
      (node (ref "U1200") (pin "C4") (pinfunction "PE0_C4") (pintype "passive"))
    )
    (net (code "199") (name "Net-(U1200A-PE1)") (class "Default")
      (node (ref "R1335") (pin "1") (pinfunction "1_1") (pintype "passive"))
      (node (ref "U1200") (pin "B4") (pinfunction "PE1_B4") (pintype "passive"))
    )
    (net (code "200") (name "Net-(U1200A-PE2)") (class "Default")
      (node (ref "R1337") (pin "1") (pinfunction "1_1") (pintype "passive"))
      (node (ref "U1200") (pin "C3") (pinfunction "PE2_C3") (pintype "passive"))
    )
    (net (code "201") (name "Net-(U1200A-PE3)") (class "Default")
      (node (ref "R1339") (pin "1") (pinfunction "1_1") (pintype "passive"))
      (node (ref "U1200") (pin "D3") (pinfunction "PE3_D3") (pintype "passive"))
    )
    (net (code "202") (name "Net-(U1200A-PE4)") (class "Default")
      (node (ref "R1340") (pin "1") (pinfunction "1_1") (pintype "passive"))
      (node (ref "U1200") (pin "D2") (pinfunction "PE4_D2") (pintype "passive"))
    )
    (net (code "203") (name "Net-(U1200A-PE5)") (class "Default")
      (node (ref "R1342") (pin "1") (pinfunction "1_1") (pintype "passive"))
      (node (ref "U1200") (pin "D1") (pinfunction "PE5_D1") (pintype "passive"))
    )
    (net (code "204") (name "Net-(U1200A-PE6)") (class "Default")
      (node (ref "R1344") (pin "1") (pinfunction "1_1") (pintype "passive"))
      (node (ref "U1200") (pin "E5") (pinfunction "PE6_E5") (pintype "passive"))
    )
    (net (code "205") (name "Net-(U1200A-PE7)") (class "Default")
      (node (ref "R1346") (pin "1") (pinfunction "1_1") (pintype "passive"))
      (node (ref "U1200") (pin "U9") (pinfunction "PE7_U9") (pintype "passive"))
    )
    (net (code "206") (name "Net-(U1200A-PE8)") (class "Default")
      (node (ref "R1348") (pin "1") (pinfunction "1_1") (pintype "passive"))
      (node (ref "U1200") (pin "T9") (pinfunction "PE8_T9") (pintype "passive"))
    )
    (net (code "207") (name "Net-(U1200A-PE9)") (class "Default")
      (node (ref "R1350") (pin "1") (pinfunction "1_1") (pintype "passive"))
      (node (ref "U1200") (pin "P9") (pinfunction "PE9_P9") (pintype "passive"))
    )
    (net (code "208") (name "Net-(U1200A-PE10)") (class "Default")
      (node (ref "R1352") (pin "1") (pinfunction "1_1") (pintype "passive"))
      (node (ref "U1200") (pin "N9") (pinfunction "PE10_N9") (pintype "passive"))
    )
    (net (code "209") (name "Net-(U1200A-PE11)") (class "Default")
      (node (ref "R1354") (pin "1") (pinfunction "1_1") (pintype "passive"))
      (node (ref "U1200") (pin "P10") (pinfunction "PE11_P10") (pintype "passive"))
    )
    (net (code "210") (name "Net-(U1200A-PE12)") (class "Default")
      (node (ref "R1356") (pin "1") (pinfunction "1_1") (pintype "passive"))
      (node (ref "U1200") (pin "R10") (pinfunction "PE12_R10") (pintype "passive"))
    )
    (net (code "211") (name "Net-(U1200A-PE13)") (class "Default")
      (node (ref "R1358") (pin "1") (pinfunction "1_1") (pintype "passive"))
      (node (ref "U1200") (pin "T10") (pinfunction "PE13_T10") (pintype "passive"))
    )
    (net (code "212") (name "Net-(U1200A-PE14)") (class "Default")
      (node (ref "R1360") (pin "1") (pinfunction "1_1") (pintype "passive"))
      (node (ref "U1200") (pin "U10") (pinfunction "PE14_U10") (pintype "passive"))
    )
    (net (code "213") (name "Net-(U1200A-PE15)") (class "Default")
      (node (ref "R1361") (pin "1") (pinfunction "1_1") (pintype "passive"))
      (node (ref "U1200") (pin "R11") (pinfunction "PE15_R11") (pintype "passive"))
    )
    (net (code "214") (name "Net-(U1200A-PF0)") (class "Default")
      (node (ref "R1363") (pin "1") (pinfunction "1_1") (pintype "passive"))
      (node (ref "U1200") (pin "G4") (pinfunction "PF0_G4") (pintype "passive"))
    )
    (net (code "215") (name "Net-(U1200A-PF1)") (class "Default")
      (node (ref "R1365") (pin "1") (pinfunction "1_1") (pintype "passive"))
      (node (ref "U1200") (pin "G3") (pinfunction "PF1_G3") (pintype "passive"))
    )
    (net (code "216") (name "Net-(U1200A-PF2)") (class "Default")
      (node (ref "R1366") (pin "1") (pinfunction "1_1") (pintype "passive"))
      (node (ref "U1200") (pin "G1") (pinfunction "PF2_G1") (pintype "passive"))
    )
    (net (code "217") (name "Net-(U1200A-PF3)") (class "Default")
      (node (ref "R1367") (pin "1") (pinfunction "1_1") (pintype "passive"))
      (node (ref "U1200") (pin "H4") (pinfunction "PF3_H4") (pintype "passive"))
    )
    (net (code "218") (name "Net-(U1200A-PF4)") (class "Default")
      (node (ref "R1368") (pin "1") (pinfunction "1_1") (pintype "passive"))
      (node (ref "U1200") (pin "J5") (pinfunction "PF4_J5") (pintype "passive"))
    )
    (net (code "219") (name "Net-(U1200A-PF5)") (class "Default")
      (node (ref "R1369") (pin "1") (pinfunction "1_1") (pintype "passive"))
      (node (ref "U1200") (pin "J4") (pinfunction "PF5_J4") (pintype "passive"))
    )
    (net (code "220") (name "Net-(U1200A-PF6)") (class "Default")
      (node (ref "R1370") (pin "1") (pinfunction "1_1") (pintype "passive"))
      (node (ref "U1200") (pin "K2") (pinfunction "PF6_K2") (pintype "passive"))
    )
    (net (code "221") (name "Net-(U1200A-PF7)") (class "Default")
      (node (ref "R1371") (pin "1") (pinfunction "1_1") (pintype "passive"))
      (node (ref "U1200") (pin "K3") (pinfunction "PF7_K3") (pintype "passive"))
    )
    (net (code "222") (name "Net-(U1200A-PF8)") (class "Default")
      (node (ref "R1373") (pin "1") (pinfunction "1_1") (pintype "passive"))
      (node (ref "U1200") (pin "K4") (pinfunction "PF8_K4") (pintype "passive"))
    )
    (net (code "223") (name "Net-(U1200A-PF9)") (class "Default")
      (node (ref "R1374") (pin "1") (pinfunction "1_1") (pintype "passive"))
      (node (ref "U1200") (pin "L4") (pinfunction "PF9_L4") (pintype "passive"))
    )
    (net (code "224") (name "Net-(U1200A-PF10)") (class "Default")
      (node (ref "R1375") (pin "1") (pinfunction "1_1") (pintype "passive"))
      (node (ref "U1200") (pin "L3") (pinfunction "PF10_L3") (pintype "passive"))
    )
    (net (code "225") (name "Net-(U1200A-PF11)") (class "Default")
      (node (ref "R1378") (pin "1") (pinfunction "1_1") (pintype "passive"))
      (node (ref "U1200") (pin "T7") (pinfunction "PF11_T7") (pintype "passive"))
    )
    (net (code "226") (name "Net-(U1200A-PF12)") (class "Default")
      (node (ref "R1379") (pin "1") (pinfunction "1_1") (pintype "passive"))
      (node (ref "U1200") (pin "R7") (pinfunction "PF12_R7") (pintype "passive"))
    )
    (net (code "227") (name "Net-(U1200A-PF13)") (class "Default")
      (node (ref "R1380") (pin "1") (pinfunction "1_1") (pintype "passive"))
      (node (ref "U1200") (pin "P7") (pinfunction "PF13_P7") (pintype "passive"))
    )
    (net (code "228") (name "Net-(U1200A-PF14)") (class "Default")
      (node (ref "R1382") (pin "1") (pinfunction "1_1") (pintype "passive"))
      (node (ref "U1200") (pin "P8") (pinfunction "PF14_P8") (pintype "passive"))
    )
    (net (code "229") (name "Net-(U1200A-PF15)") (class "Default")
      (node (ref "R1384") (pin "1") (pinfunction "1_1") (pintype "passive"))
      (node (ref "U1200") (pin "R9") (pinfunction "PF15_R9") (pintype "passive"))
    )
    (net (code "230") (name "Net-(U1200B-PG0)") (class "Default")
      (node (ref "R1301") (pin "1") (pinfunction "1_1") (pintype "passive"))
      (node (ref "U1200") (pin "T8") (pinfunction "PG0_T8") (pintype "passive"))
    )
    (net (code "231") (name "Net-(U1200B-PG1)") (class "Default")
      (node (ref "R1304") (pin "1") (pinfunction "1_1") (pintype "passive"))
      (node (ref "U1200") (pin "U8") (pinfunction "PG1_U8") (pintype "passive"))
    )
    (net (code "232") (name "Net-(U1200B-PG4)") (class "Default")
      (node (ref "R1309") (pin "1") (pinfunction "1_1") (pintype "passive"))
      (node (ref "U1200") (pin "H14") (pinfunction "PG4_H14") (pintype "passive"))
    )
    (net (code "233") (name "Net-(U1200B-PG5)") (class "Default")
      (node (ref "R1312") (pin "1") (pinfunction "1_1") (pintype "passive"))
      (node (ref "U1200") (pin "G14") (pinfunction "PG5_G14") (pintype "passive"))
    )
    (net (code "234") (name "Net-(U1200B-PG8)") (class "Default")
      (node (ref "R1318") (pin "1") (pinfunction "1_1") (pintype "passive"))
      (node (ref "U1200") (pin "F15") (pinfunction "PG8_F15") (pintype "passive"))
    )
    (net (code "235") (name "Net-(U1200B-PG9)") (class "Default")
      (node (ref "R1321") (pin "1") (pinfunction "1_1") (pintype "passive"))
      (node (ref "U1200") (pin "A10") (pinfunction "PG9_A10") (pintype "passive"))
    )
    (net (code "236") (name "Net-(U1200B-PG14)") (class "Default")
      (node (ref "R1330") (pin "1") (pinfunction "1_1") (pintype "passive"))
      (node (ref "U1200") (pin "D8") (pinfunction "PG14_D8") (pintype "passive"))
    )
    (net (code "237") (name "Net-(U1200B-PG15)") (class "Default")
      (node (ref "R1332") (pin "1") (pinfunction "1_1") (pintype "passive"))
      (node (ref "U1200") (pin "D6") (pinfunction "PG15_D6") (pintype "passive"))
    )
    (net (code "238") (name "Net-(U1200B-PH0-OSCIN)") (class "Default")
      (node (ref "R1376") (pin "1") (pinfunction "1_1") (pintype "passive"))
      (node (ref "U1200") (pin "J2") (pinfunction "PH0-OSCIN_J2") (pintype "passive"))
    )
    (net (code "239") (name "Net-(U1200B-PH2)") (class "Default")
      (node (ref "R1334") (pin "1") (pinfunction "1_1") (pintype "passive"))
      (node (ref "U1200") (pin "N2") (pinfunction "PH2_N2") (pintype "passive"))
    )
    (net (code "240") (name "Net-(U1200B-PH3)") (class "Default")
      (node (ref "R1336") (pin "1") (pinfunction "1_1") (pintype "passive"))
      (node (ref "U1200") (pin "P2") (pinfunction "PH3_P2") (pintype "passive"))
    )
    (net (code "241") (name "Net-(U1200B-PH6)") (class "Default")
      (node (ref "R1341") (pin "1") (pinfunction "1_1") (pintype "passive"))
      (node (ref "U1200") (pin "T11") (pinfunction "PH6_T11") (pintype "passive"))
    )
    (net (code "242") (name "Net-(U1200B-PH7)") (class "Default")
      (node (ref "R1343") (pin "1") (pinfunction "1_1") (pintype "passive"))
      (node (ref "U1200") (pin "U13") (pinfunction "PH7_U13") (pintype "passive"))
    )
    (net (code "243") (name "Net-(U1200B-PH8)") (class "Default")
      (node (ref "R1345") (pin "1") (pinfunction "1_1") (pintype "passive"))
      (node (ref "U1200") (pin "T13") (pinfunction "PH8_T13") (pintype "passive"))
    )
    (net (code "244") (name "Net-(U1200B-PH9)") (class "Default")
      (node (ref "R1347") (pin "1") (pinfunction "1_1") (pintype "passive"))
      (node (ref "U1200") (pin "R13") (pinfunction "PH9_R13") (pintype "passive"))
    )
    (net (code "245") (name "Net-(U1200B-PH10)") (class "Default")
      (node (ref "R1349") (pin "1") (pinfunction "1_1") (pintype "passive"))
      (node (ref "U1200") (pin "P13") (pinfunction "PH10_P13") (pintype "passive"))
    )
    (net (code "246") (name "Net-(U1200B-PH11)") (class "Default")
      (node (ref "R1351") (pin "1") (pinfunction "1_1") (pintype "passive"))
      (node (ref "U1200") (pin "P14") (pinfunction "PH11_P14") (pintype "passive"))
    )
    (net (code "247") (name "Net-(U1200B-PH12)") (class "Default")
      (node (ref "R1353") (pin "1") (pinfunction "1_1") (pintype "passive"))
      (node (ref "U1200") (pin "R14") (pinfunction "PH12_R14") (pintype "passive"))
    )
    (net (code "248") (name "Net-(U1200B-PH13)") (class "Default")
      (node (ref "R1355") (pin "1") (pinfunction "1_1") (pintype "passive"))
      (node (ref "U1200") (pin "D16") (pinfunction "PH13_D16") (pintype "passive"))
    )
    (net (code "249") (name "Net-(U1200B-PH14)") (class "Default")
      (node (ref "R1357") (pin "1") (pinfunction "1_1") (pintype "passive"))
      (node (ref "U1200") (pin "B17") (pinfunction "PH14_B17") (pintype "passive"))
    )
    (net (code "250") (name "Net-(U1200B-PH15)") (class "Default")
      (node (ref "R1359") (pin "1") (pinfunction "1_1") (pintype "passive"))
      (node (ref "U1200") (pin "B16") (pinfunction "PH15_B16") (pintype "passive"))
    )
    (net (code "251") (name "Net-(U1200B-PI0)") (class "Default")
      (node (ref "R1302") (pin "1") (pinfunction "1_1") (pintype "passive"))
      (node (ref "U1200") (pin "A16") (pinfunction "PI0_A16") (pintype "passive"))
    )
    (net (code "252") (name "Net-(U1200B-PI1)") (class "Default")
      (node (ref "R1305") (pin "1") (pinfunction "1_1") (pintype "passive"))
      (node (ref "U1200") (pin "A15") (pinfunction "PI1_A15") (pintype "passive"))
    )
    (net (code "253") (name "Net-(U1200B-PI2)") (class "Default")
      (node (ref "R1306") (pin "1") (pinfunction "1_1") (pintype "passive"))
      (node (ref "U1200") (pin "B15") (pinfunction "PI2_B15") (pintype "passive"))
    )
    (net (code "254") (name "Net-(U1200B-PI3)") (class "Default")
      (node (ref "R1307") (pin "1") (pinfunction "1_1") (pintype "passive"))
      (node (ref "U1200") (pin "C14") (pinfunction "PI3_C14") (pintype "passive"))
    )
    (net (code "255") (name "Net-(U1200B-PI4)") (class "Default")
      (node (ref "R1310") (pin "1") (pinfunction "1_1") (pintype "passive"))
      (node (ref "U1200") (pin "A4") (pinfunction "PI4_A4") (pintype "passive"))
    )
    (net (code "256") (name "Net-(U1200B-PI5)") (class "Default")
      (node (ref "R1313") (pin "1") (pinfunction "1_1") (pintype "passive"))
      (node (ref "U1200") (pin "A3") (pinfunction "PI5_A3") (pintype "passive"))
    )
    (net (code "257") (name "Net-(U1200B-PI6)") (class "Default")
      (node (ref "R1314") (pin "1") (pinfunction "1_1") (pintype "passive"))
      (node (ref "U1200") (pin "A2") (pinfunction "PI6_A2") (pintype "passive"))
    )
    (net (code "258") (name "Net-(U1200B-PI7)") (class "Default")
      (node (ref "R1316") (pin "1") (pinfunction "1_1") (pintype "passive"))
      (node (ref "U1200") (pin "B3") (pinfunction "PI7_B3") (pintype "passive"))
    )
    (net (code "259") (name "Net-(U1200B-PI9)") (class "Default")
      (node (ref "R1322") (pin "1") (pinfunction "1_1") (pintype "passive"))
      (node (ref "U1200") (pin "E2") (pinfunction "PI9_E2") (pintype "passive"))
    )
    (net (code "260") (name "Net-(U1200B-PI10)") (class "Default")
      (node (ref "R1325") (pin "1") (pinfunction "1_1") (pintype "passive"))
      (node (ref "U1200") (pin "F3") (pinfunction "PI10_F3") (pintype "passive"))
    )
    (net (code "261") (name "Net-(Y1300-ED)") (class "Default")
      (node (ref "R1386") (pin "2") (pinfunction "2_2") (pintype "passive"))
      (node (ref "Y1300") (pin "1") (pinfunction "ED_1") (pintype "passive"))
    )
    (net (code "262") (name "Net-(Y1300-OUT)") (class "Default")
      (node (ref "R1376") (pin "2") (pinfunction "2_2") (pintype "passive"))
      (node (ref "Y1300") (pin "3") (pinfunction "OUT_3") (pintype "passive"))
    )
    (net (code "263") (name "Net-(Y1301-ED)") (class "Default")
      (node (ref "R1387") (pin "2") (pinfunction "2_2") (pintype "passive"))
      (node (ref "Y1301") (pin "1") (pinfunction "ED_1") (pintype "passive"))
    )
    (net (code "264") (name "Net-(Y1301-OUT)") (class "Default")
      (node (ref "R1381") (pin "1") (pinfunction "1_1") (pintype "passive"))
      (node (ref "Y1301") (pin "3") (pinfunction "OUT_3") (pintype "passive"))
    )
    (net (code "265") (name "VMCU") (class "Default")
      (node (ref "C1302") (pin "2") (pinfunction "2_2") (pintype "passive"))
      (node (ref "C1303") (pin "1") (pinfunction "1_1") (pintype "passive"))
      (node (ref "C1304") (pin "1") (pinfunction "1_1") (pintype "passive"))
      (node (ref "C1305") (pin "1") (pinfunction "1_1") (pintype "passive"))
      (node (ref "R1372") (pin "1") (pinfunction "1_1") (pintype "passive"))
      (node (ref "R1383") (pin "2") (pinfunction "2_2") (pintype "passive"))
      (node (ref "R1386") (pin "1") (pinfunction "1_1") (pintype "passive"))
      (node (ref "R1387") (pin "1") (pinfunction "1_1") (pintype "passive"))
      (node (ref "U1301") (pin "5") (pinfunction "VCC_5") (pintype "passive"))
      (node (ref "Y1300") (pin "4") (pinfunction "VDD_4") (pintype "passive"))
      (node (ref "Y1301") (pin "4") (pinfunction "VDD_4") (pintype "passive"))
    )
    (net (code "266") (name "unconnected-(TP1300-Pad0)") (class "Default")
      (node (ref "TP1300") (pin "0") (pintype "passive"))
    )
    (net (code "267") (name "unconnected-(U1200A-PB2-PadR6)") (class "Default")
      (node (ref "U1200") (pin "R6") (pinfunction "PB2_R6") (pintype "passive+no_connect"))
    )
    (net (code "268") (name "unconnected-(U1200A-PB5-PadA5)") (class "Default")
      (node (ref "U1200") (pin "A5") (pinfunction "PB5_A5") (pintype "passive+no_connect"))
    )
    (net (code "269") (name "unconnected-(U1200A-PB12-PadT14)") (class "Default")
      (node (ref "U1200") (pin "T14") (pinfunction "PB12_T14") (pintype "passive+no_connect"))
    )
    (net (code "270") (name "unconnected-(U1200A-PB13-PadU14)") (class "Default")
      (node (ref "U1200") (pin "U14") (pinfunction "PB13_U14") (pintype "passive+no_connect"))
    )
    (net (code "271") (name "unconnected-(U1200A-PC8-PadE13)") (class "Default")
      (node (ref "U1200") (pin "E13") (pinfunction "PC8_E13") (pintype "passive+no_connect"))
    )
    (net (code "272") (name "unconnected-(U1200A-PC10-PadA13)") (class "Default")
      (node (ref "U1200") (pin "A13") (pinfunction "PC10_A13") (pintype "passive+no_connect"))
    )
    (net (code "273") (name "unconnected-(U1200A-PC13-PadE3)") (class "Default")
      (node (ref "U1200") (pin "E3") (pinfunction "PC13_E3") (pintype "passive+no_connect"))
    )
    (net (code "274") (name "unconnected-(U1200A-PC15-OSC32_OUT-PadC1)") (class "Default")
      (node (ref "U1200") (pin "C1") (pinfunction "PC15-OSC32_OUT_C1") (pintype "passive+no_connect"))
    )
    (net (code "275") (name "unconnected-(U1200A-PD4-PadA12)") (class "Default")
      (node (ref "U1200") (pin "A12") (pinfunction "PD4_A12") (pintype "passive+no_connect"))
    )
    (net (code "276") (name "unconnected-(U1200B-PC2_C-PadR1)") (class "Default")
      (node (ref "U1200") (pin "R1") (pinfunction "PC2_C_R1") (pintype "passive+no_connect"))
    )
    (net (code "277") (name "unconnected-(U1200B-PC3_C-PadR2)") (class "Default")
      (node (ref "U1200") (pin "R2") (pinfunction "PC3_C_R2") (pintype "passive+no_connect"))
    )
    (net (code "278") (name "unconnected-(U1200B-PG3-PadH15)") (class "Default")
      (node (ref "U1200") (pin "H15") (pinfunction "PG3_H15") (pintype "passive"))
    )
    (net (code "279") (name "unconnected-(U1200B-PH1-OSCOUT-PadJ1)") (class "Default")
      (node (ref "U1200") (pin "J1") (pinfunction "PH1-OSCOUT_J1") (pintype "passive+no_connect"))
    )
    (net (code "280") (name "unconnected-(U1200B-PJ5-PadR12)") (class "Default")
      (node (ref "U1200") (pin "R12") (pinfunction "PJ5_R12") (pintype "passive+no_connect"))
    )
    (net (code "281") (name "unconnected-(U1200B-PJ6-PadN15)") (class "Default")
      (node (ref "U1200") (pin "N15") (pinfunction "PJ6_N15") (pintype "passive+no_connect"))
    )
    (net (code "282") (name "unconnected-(U1200B-PJ8-PadN13)") (class "Default")
      (node (ref "U1200") (pin "N13") (pinfunction "PJ8_N13") (pintype "passive+no_connect"))
    )
  )
)
